# RN2483.net
KiCad netlist of a schematic drawn in Altium Designer
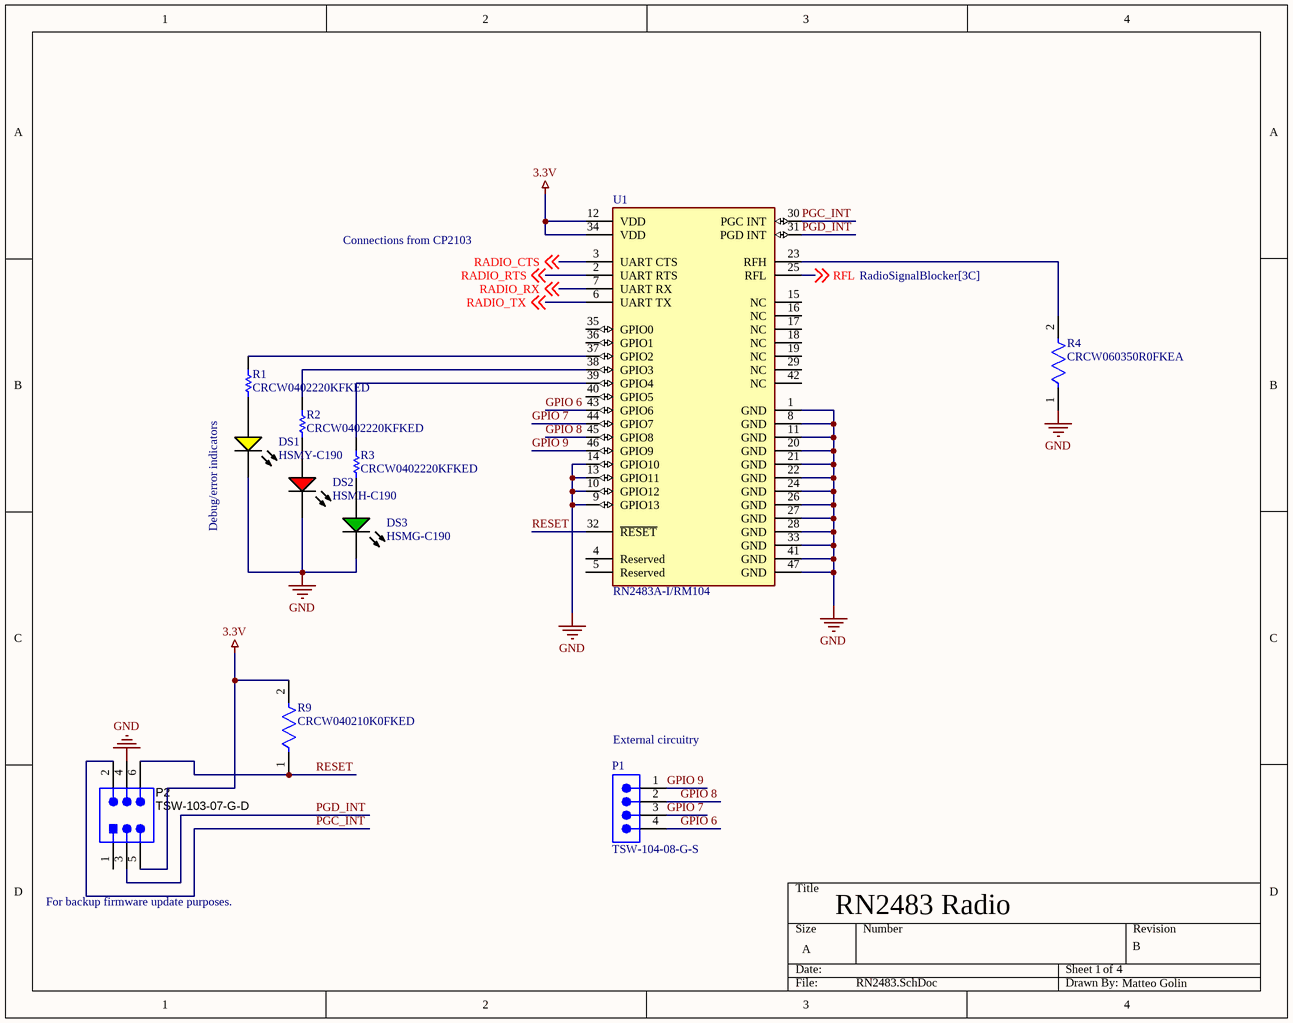
[diagram p0: RN2483.SchDoc]

(export (version "E")
  (design (tool "Eeschema 10.0.6"))
  (components
    (comp (ref "DS1")
      (value "HSMY-C190")
      (footprint "AVAG-HSMX-C190_V")
      (description "LED Uni-Color Yellow, 65 mW, 20 mA, -40 to 85 degC, 2-Pin SMD, RoHS, Tape and Reel")
      (fields (field (name "TOLERANCE") "1%"))
      (libsource (lib "Altium Content Vault") (part "LED-YELLOW-AK-2"))
    )
    (comp (ref "DS2")
      (value "HSMH-C190")
      (footprint "AVAG-HSMX-C190_V")
      (description "LED Uni-Color Red, 65 mW, 20 mA, -40 to 85 degC, 2-Pin SMD, RoHS, Tape and Reel")
      (libsource (lib "Altium Content Vault") (part "LED-RED-AK-2"))
    )
    (comp (ref "DS3")
      (value "HSMG-C190")
      (footprint "AVAG-HSMX-C190_V")
      (description "Chip LED, Green, 2.2 V, -40 to 85 degC, 2-Pin SMD, RoHS, Tape and Reel")
      (libsource (lib "Altium Content Vault") (part "LED-GREEN-AK-2"))
    )
    (comp (ref "P1")
      (value "TSW-104-08-G-S")
      (footprint "SMTC-TSW-104-08-X-S")
      (description "0.025\" SQ Post Header, Through-hole, Vertical, -55 to 125 degC, 2.54 mm Pitch, 4-Pin, Male, RoHS")
      (fields (field (name "MANUFACTURER") "Samtec"))
      (libsource (lib "Altium Content Vault") (part "SMTC-TSW-104-08-X-S"))
    )
    (comp (ref "P2")
      (value "TSW-103-07-G-D")
      (footprint "SMTC-TSW-103-07-G-D_V")
      (fields (field (name "MANUFACTURER") "Samtec-Inc."))
      (libsource (lib "Altium Content Vault") (part "CN-2P-M-R6"))
    )
    (comp (ref "R1")
      (value "CRCW0402220KFKED")
      (footprint "RESC1005X40X25LL05T05")
      (fields (field (name "MANUFACTURER") "Vishay Dale"))
      (libsource (lib "Altium Content Vault") (part "RES"))
    )
    (comp (ref "R2")
      (value "CRCW0402220KFKED")
      (footprint "RESC1005X40X25LL05T05")
      (fields (field (name "MANUFACTURER") "Vishay Dale"))
      (libsource (lib "Altium Content Vault") (part "RES"))
    )
    (comp (ref "R3")
      (value "CRCW0402220KFKED")
      (footprint "RESC1005X40X25LL05T05")
      (fields (field (name "MANUFACTURER") "Vishay Dale"))
      (libsource (lib "Altium Content Vault") (part "RES"))
    )
    (comp (ref "R4")
      (value "CRCW060350R0FKEA")
      (footprint "FP-CRCW0603-e3-MFG")
      (description "RES Thick Film, 50Ω, 1%, 0.1W, 100ppm/°C, 0603")
      (fields (field (name "TOLERANCE") "1%"))
      (libsource (lib "Altium Content Vault") (part "1029c3af85768c4190bb7ad29bc67b5"))
    )
    (comp (ref "R9")
      (value "CRCW040210K0FKED")
      (footprint "FP-CRCW0402-e3-IPC_B")
      (description "RES SMD 10K OHM 1% 1/16W 0402")
      (fields (field (name "TOLERANCE") "1%"))
      (libsource (lib "Altium Content Vault") (part "1029c3af85768c4190bb7ad29bc67b5"))
    )
    (comp (ref "U1")
      (value "RN2483A-I/RM104")
      (footprint "FP-RN2483A-I-RM104-MFG")
      (fields
        (field (name "OCTOPART") "https://octopart.com/rn2483a-i%2Frm104-microchip-90584481")
        (field (name "MANUFACTURER") "Microchip")
      )
      (libsource (lib "Altium Content Vault") (part "630a5bff3a952dd521c0edb04079da7"))
    )
  )
  (nets
    (net (code "1") (name "/GPIO 6") (class "Default")
      (node (ref "P1") (pin "4") (pinfunction "4_4") (pintype "passive"))
      (node (ref "U1") (pin "43") (pinfunction "GPIO6_43") (pintype "bidirectional"))
    )
    (net (code "2") (name "/GPIO 7") (class "Default")
      (node (ref "P1") (pin "3") (pinfunction "3_3") (pintype "passive"))
      (node (ref "U1") (pin "44") (pinfunction "GPIO7_44") (pintype "bidirectional"))
    )
    (net (code "3") (name "/GPIO 8") (class "Default")
      (node (ref "P1") (pin "2") (pinfunction "2_2") (pintype "passive"))
      (node (ref "U1") (pin "45") (pinfunction "GPIO8_45") (pintype "bidirectional"))
    )
    (net (code "4") (name "/GPIO 9") (class "Default")
      (node (ref "P1") (pin "1") (pinfunction "1_1") (pintype "passive"))
      (node (ref "U1") (pin "46") (pinfunction "GPIO9_46") (pintype "bidirectional"))
    )
    (net (code "5") (name "/PGC_INT") (class "Default")
      (node (ref "P2") (pin "2") (pinfunction "2_2") (pintype "passive"))
      (node (ref "U1") (pin "30") (pinfunction "PGC_INT_30") (pintype "bidirectional"))
    )
    (net (code "6") (name "/PGD_INT") (class "Default")
      (node (ref "P2") (pin "3") (pinfunction "3_3") (pintype "passive"))
      (node (ref "U1") (pin "31") (pinfunction "PGD_INT_31") (pintype "bidirectional"))
    )
    (net (code "7") (name "/RESET") (class "Default")
      (node (ref "P2") (pin "6") (pinfunction "6_6") (pintype "passive"))
      (node (ref "R9") (pin "1") (pinfunction "1_1") (pintype "passive"))
      (node (ref "U1") (pin "32") (pinfunction "~{RESET}_32") (pintype "passive"))
    )
    (net (code "8") (name "3.3V") (class "Default")
      (node (ref "P2") (pin "5") (pinfunction "5_5") (pintype "passive"))
      (node (ref "R9") (pin "2") (pinfunction "2_2") (pintype "passive"))
      (node (ref "U1") (pin "12") (pinfunction "VDD_12") (pintype "passive"))
      (node (ref "U1") (pin "34") (pinfunction "VDD_34") (pintype "passive"))
    )
    (net (code "9") (name "GND") (class "Default")
      (node (ref "DS1") (pin "2") (pinfunction "K_2") (pintype "passive"))
      (node (ref "DS2") (pin "2") (pinfunction "K_2") (pintype "passive"))
      (node (ref "DS3") (pin "2") (pinfunction "K_2") (pintype "passive"))
      (node (ref "P2") (pin "4") (pinfunction "4_4") (pintype "passive"))
      (node (ref "R4") (pin "1") (pinfunction "1_1") (pintype "passive"))
      (node (ref "U1") (pin "1") (pinfunction "GND_1") (pintype "passive"))
      (node (ref "U1") (pin "10") (pinfunction "GPIO12_10") (pintype "bidirectional"))
      (node (ref "U1") (pin "11") (pinfunction "GND_11") (pintype "passive"))
      (node (ref "U1") (pin "13") (pinfunction "GPIO11_13") (pintype "bidirectional"))
      (node (ref "U1") (pin "14") (pinfunction "GPIO10_14") (pintype "bidirectional"))
      (node (ref "U1") (pin "20") (pinfunction "GND_20") (pintype "passive"))
      (node (ref "U1") (pin "21") (pinfunction "GND_21") (pintype "passive"))
      (node (ref "U1") (pin "22") (pinfunction "GND_22") (pintype "passive"))
      (node (ref "U1") (pin "24") (pinfunction "GND_24") (pintype "passive"))
      (node (ref "U1") (pin "26") (pinfunction "GND_26") (pintype "passive"))
      (node (ref "U1") (pin "27") (pinfunction "GND_27") (pintype "passive"))
      (node (ref "U1") (pin "28") (pinfunction "GND_28") (pintype "passive"))
      (node (ref "U1") (pin "33") (pinfunction "GND_33") (pintype "passive"))
      (node (ref "U1") (pin "41") (pinfunction "GND_41") (pintype "passive"))
      (node (ref "U1") (pin "47") (pinfunction "GND_47") (pintype "passive"))
      (node (ref "U1") (pin "8") (pinfunction "GND_8") (pintype "passive"))
      (node (ref "U1") (pin "9") (pinfunction "GPIO13_9") (pintype "bidirectional"))
    )
    (net (code "10") (name "Net-(DS1-A)") (class "Default")
      (node (ref "DS1") (pin "1") (pinfunction "A_1") (pintype "passive"))
      (node (ref "R1") (pin "1") (pinfunction "1_1") (pintype "passive"))
    )
    (net (code "11") (name "Net-(DS2-A)") (class "Default")
      (node (ref "DS2") (pin "1") (pinfunction "A_1") (pintype "passive"))
      (node (ref "R2") (pin "1") (pinfunction "1_1") (pintype "passive"))
    )
    (net (code "12") (name "Net-(DS3-A)") (class "Default")
      (node (ref "DS3") (pin "1") (pinfunction "A_1") (pintype "passive"))
      (node (ref "R3") (pin "1") (pinfunction "1_1") (pintype "passive"))
    )
    (net (code "13") (name "Net-(U1-GPIO2)") (class "Default")
      (node (ref "R1") (pin "2") (pinfunction "2_2") (pintype "passive"))
      (node (ref "U1") (pin "37") (pinfunction "GPIO2_37") (pintype "bidirectional"))
    )
    (net (code "14") (name "Net-(U1-GPIO3)") (class "Default")
      (node (ref "R2") (pin "2") (pinfunction "2_2") (pintype "passive"))
      (node (ref "U1") (pin "38") (pinfunction "GPIO3_38") (pintype "bidirectional"))
    )
    (net (code "15") (name "Net-(U1-GPIO4)") (class "Default")
      (node (ref "R3") (pin "2") (pinfunction "2_2") (pintype "passive"))
      (node (ref "U1") (pin "39") (pinfunction "GPIO4_39") (pintype "bidirectional"))
    )
    (net (code "16") (name "Net-(U1-RFH)") (class "Default")
      (node (ref "R4") (pin "2") (pinfunction "2_2") (pintype "passive"))
      (node (ref "U1") (pin "23") (pinfunction "RFH_23") (pintype "passive"))
    )
    (net (code "17") (name "RADIO_CTS") (class "Default")
      (node (ref "U1") (pin "3") (pinfunction "UART_CTS_3") (pintype "passive"))
    )
    (net (code "18") (name "RADIO_RTS") (class "Default")
      (node (ref "U1") (pin "2") (pinfunction "UART_RTS_2") (pintype "passive"))
    )
    (net (code "19") (name "RADIO_RX") (class "Default")
      (node (ref "U1") (pin "7") (pinfunction "UART_RX_7") (pintype "passive"))
    )
    (net (code "20") (name "RADIO_TX") (class "Default")
      (node (ref "U1") (pin "6") (pinfunction "UART_TX_6") (pintype "passive"))
    )
    (net (code "21") (name "RFL") (class "Default")
      (node (ref "U1") (pin "25") (pinfunction "RFL_25") (pintype "passive"))
    )
    (net (code "22") (name "unconnected-(P2-Pad1)") (class "Default")
      (node (ref "P2") (pin "1") (pinfunction "1_1") (pintype "passive"))
    )
    (net (code "23") (name "unconnected-(U1-GPIO0-Pad35)") (class "Default")
      (node (ref "U1") (pin "35") (pinfunction "GPIO0_35") (pintype "bidirectional"))
    )
    (net (code "24") (name "unconnected-(U1-GPIO1-Pad36)") (class "Default")
      (node (ref "U1") (pin "36") (pinfunction "GPIO1_36") (pintype "bidirectional"))
    )
    (net (code "25") (name "unconnected-(U1-GPIO5-Pad40)") (class "Default")
      (node (ref "U1") (pin "40") (pinfunction "GPIO5_40") (pintype "bidirectional"))
    )
    (net (code "26") (name "unconnected-(U1-NC-Pad15)") (class "Default")
      (node (ref "U1") (pin "15") (pinfunction "NC_15") (pintype "passive"))
    )
    (net (code "27") (name "unconnected-(U1-NC-Pad16)") (class "Default")
      (node (ref "U1") (pin "16") (pinfunction "NC_16") (pintype "passive"))
    )
    (net (code "28") (name "unconnected-(U1-NC-Pad17)") (class "Default")
      (node (ref "U1") (pin "17") (pinfunction "NC_17") (pintype "passive"))
    )
    (net (code "29") (name "unconnected-(U1-NC-Pad18)") (class "Default")
      (node (ref "U1") (pin "18") (pinfunction "NC_18") (pintype "passive"))
    )
    (net (code "30") (name "unconnected-(U1-NC-Pad19)") (class "Default")
      (node (ref "U1") (pin "19") (pinfunction "NC_19") (pintype "passive"))
    )
    (net (code "31") (name "unconnected-(U1-NC-Pad29)") (class "Default")
      (node (ref "U1") (pin "29") (pinfunction "NC_29") (pintype "passive"))
    )
    (net (code "32") (name "unconnected-(U1-NC-Pad42)") (class "Default")
      (node (ref "U1") (pin "42") (pinfunction "NC_42") (pintype "passive"))
    )
    (net (code "33") (name "unconnected-(U1-Reserved-Pad4)") (class "Default")
      (node (ref "U1") (pin "4") (pinfunction "Reserved_4") (pintype "passive"))
    )
    (net (code "34") (name "unconnected-(U1-Reserved-Pad5)") (class "Default")
      (node (ref "U1") (pin "5") (pinfunction "Reserved_5") (pintype "passive"))
    )
  )
)
